# Independent_Assignment.net
KiCad netlist of a schematic drawn in EAGLE
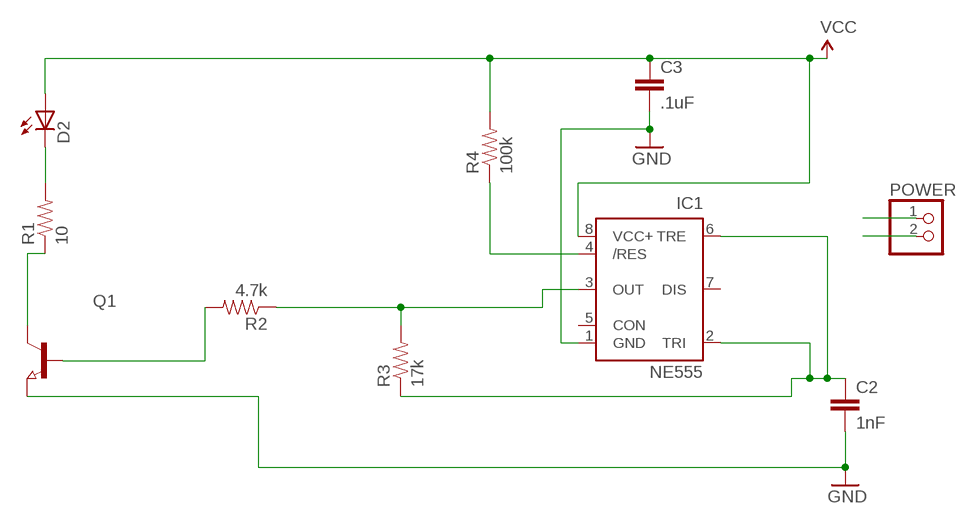
[diagram p0: schematic, sheet 1]

(export (version "E")
  (design (tool "Eeschema 10.0.6"))
  (components
    (comp (ref "C2")
      (value "1nF")
      (footprint "eagle-import:0603-CAP")
      (libsource (lib "eagle-import") (part "CAP0603-CAP"))
    )
    (comp (ref "C3")
      (value ".1uF")
      (footprint "eagle-import:0603-CAP")
      (libsource (lib "eagle-import") (part "CAP0603-CAP"))
    )
    (comp (ref "D2")
      (value "SFH482")
      (footprint "eagle-import:SFH482")
      (libsource (lib "eagle-import") (part "SFH482"))
    )
    (comp (ref "IC1")
      (value "NE555")
      (footprint "eagle-import:DIL-08")
      (fields (field (name "MF") "Arrow Electronics") (field (name "MPN") "NE555N"))
      (libsource (lib "eagle-import") (part "NE555"))
    )
    (comp (ref "POWER")
      (value "PINHD-1X2")
      (footprint "eagle-import:1X02")
      (libsource (lib "eagle-import") (part "PINHD-1X2"))
    )
    (comp (ref "Q1")
      (value "NPN-TRANSISTOR_SOT23W")
      (footprint "eagle-import:SOT23W")
      (libsource (lib "eagle-import") (part "NPN-TRANSISTOR_SOT23W"))
    )
    (comp (ref "R1")
      (value "10")
      (footprint "eagle-import:0603-RES")
      (libsource (lib "eagle-import") (part "RESISTOR0603-RES"))
    )
    (comp (ref "R2")
      (value "4.7k")
      (footprint "eagle-import:0603-RES")
      (libsource (lib "eagle-import") (part "RESISTOR0603-RES"))
    )
    (comp (ref "R3")
      (value "17k")
      (footprint "eagle-import:0603-RES")
      (libsource (lib "eagle-import") (part "RESISTOR0603-RES"))
    )
    (comp (ref "R4")
      (value "100k")
      (footprint "eagle-import:0603-RES")
      (libsource (lib "eagle-import") (part "RESISTOR0603-RES"))
    )
  )
  (nets
    (net (code "1") (name "GND") (class "Default")
      (node (ref "C2") (pin "2") (pinfunction "2_2") (pintype "passive"))
      (node (ref "C3") (pin "2") (pinfunction "2_2") (pintype "passive"))
      (node (ref "IC1") (pin "1") (pinfunction "GND_1") (pintype "power_in"))
      (node (ref "POWER") (pin "2") (pinfunction "2_2") (pintype "passive"))
      (node (ref "Q1") (pin "3") (pinfunction "E_3") (pintype "passive"))
    )
    (net (code "2") (name "Net-(D2-C)") (class "Default")
      (node (ref "D2") (pin "K") (pinfunction "C_K") (pintype "passive"))
      (node (ref "R1") (pin "2") (pinfunction "2_2") (pintype "passive"))
    )
    (net (code "3") (name "Net-(IC1-OUT)") (class "Default")
      (node (ref "IC1") (pin "3") (pinfunction "OUT_3") (pintype "output"))
      (node (ref "R2") (pin "1") (pinfunction "1_1") (pintype "passive"))
      (node (ref "R3") (pin "2") (pinfunction "2_2") (pintype "passive"))
    )
    (net (code "4") (name "Net-(IC1-TRE)") (class "Default")
      (node (ref "C2") (pin "1") (pinfunction "1_1") (pintype "passive"))
      (node (ref "IC1") (pin "2") (pinfunction "TRI_2") (pintype "input"))
      (node (ref "IC1") (pin "6") (pinfunction "TRE_6") (pintype "input"))
      (node (ref "R3") (pin "1") (pinfunction "1_1") (pintype "passive"))
    )
    (net (code "5") (name "Net-(IC1-{slash}RES)") (class "Default")
      (node (ref "IC1") (pin "4") (pinfunction "/RES_4") (pintype "input"))
      (node (ref "R4") (pin "1") (pinfunction "1_1") (pintype "passive"))
    )
    (net (code "6") (name "Net-(Q1-B)") (class "Default")
      (node (ref "Q1") (pin "1") (pinfunction "B_1") (pintype "passive"))
      (node (ref "R2") (pin "2") (pinfunction "2_2") (pintype "passive"))
    )
    (net (code "7") (name "Net-(Q1-C)") (class "Default")
      (node (ref "Q1") (pin "2") (pinfunction "C_2") (pintype "passive"))
      (node (ref "R1") (pin "1") (pinfunction "1_1") (pintype "passive"))
    )
    (net (code "8") (name "VCC") (class "Default")
      (node (ref "C3") (pin "1") (pinfunction "1_1") (pintype "passive"))
      (node (ref "D2") (pin "A") (pinfunction "A_A") (pintype "passive"))
      (node (ref "IC1") (pin "8") (pinfunction "VCC+_8") (pintype "power_in"))
      (node (ref "POWER") (pin "1") (pinfunction "1_1") (pintype "passive"))
      (node (ref "R4") (pin "2") (pinfunction "2_2") (pintype "passive"))
    )
    (net (code "9") (name "unconnected-(IC1-CON-Pad5)") (class "Default")
      (node (ref "IC1") (pin "5") (pinfunction "CON_5") (pintype "input"))
    )
    (net (code "10") (name "unconnected-(IC1-DIS-Pad7)") (class "Default")
      (node (ref "IC1") (pin "7") (pinfunction "DIS_7") (pintype "input"))
    )
  )
)
